# light.net
KiCad netlist of a schematic drawn in Altium Designer
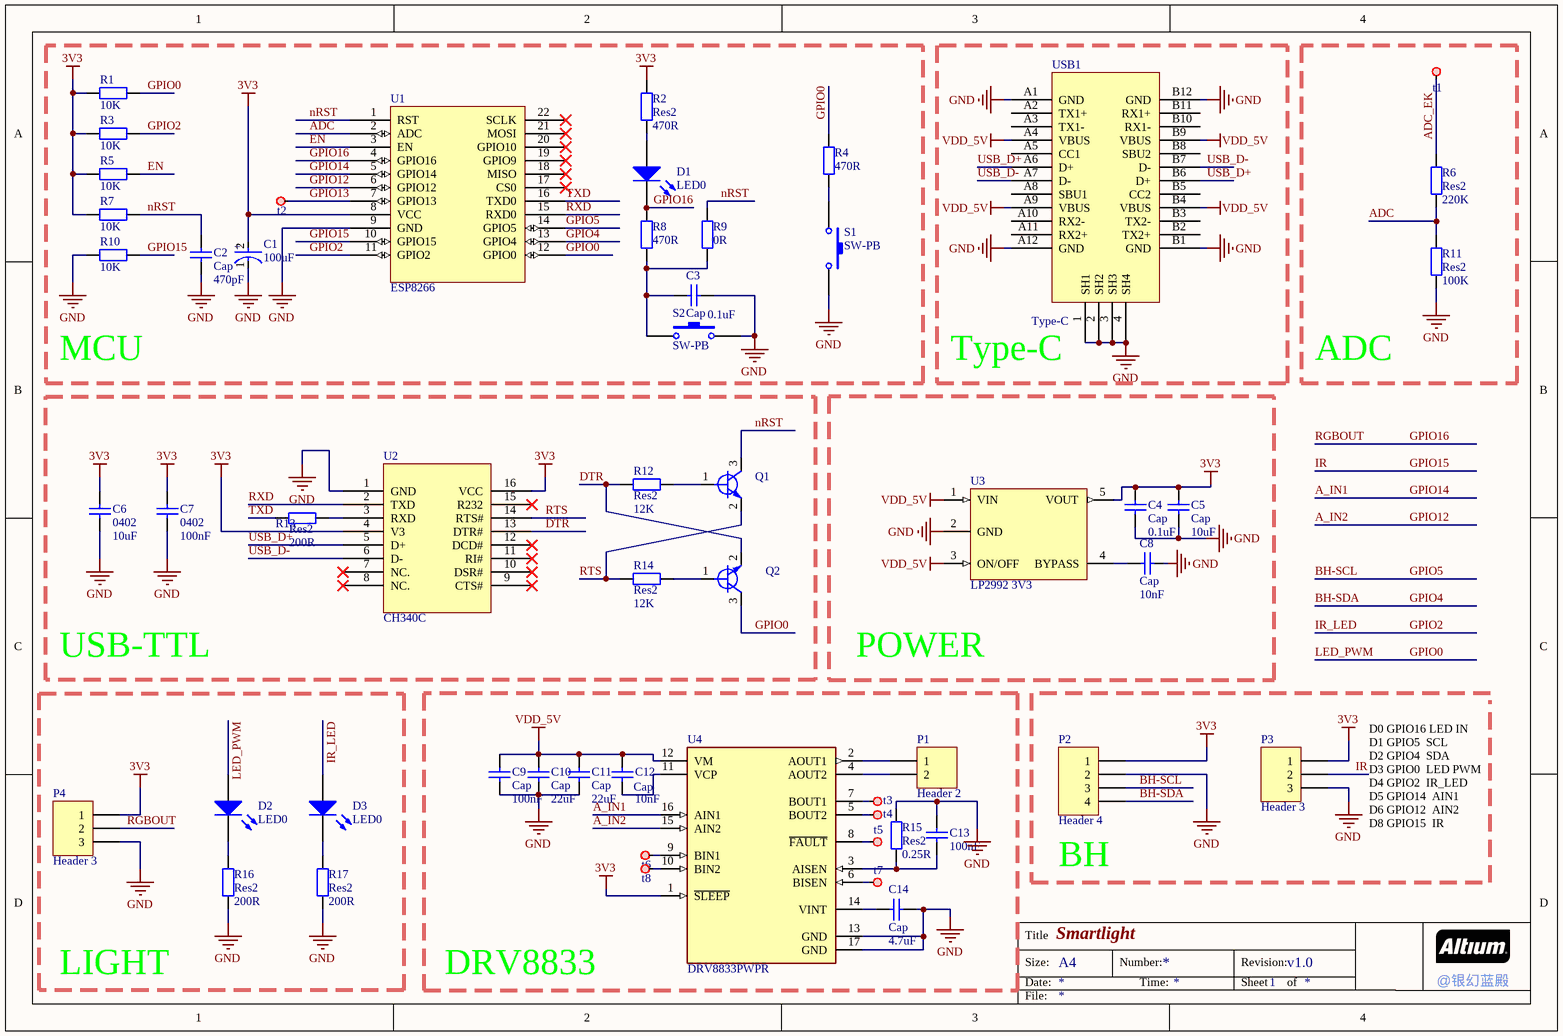
[diagram p0: light.SchDoc]

(export (version "E")
  (design (tool "Eeschema 10.0.6"))
  (components
    (comp (ref "C1")
      (value "100uF")
      (footprint "FP-T495D107K016ATE125-MFG")
      (description "CAP TANT 100UF 10% 16V 2917")
      (fields (field (name "VOLTAGE") "16V") (field (name "TOLERANCE") "10%"))
      (libsource (lib "Altium Content Vault") (part "a00bbbee19879c290e62620ae7e47b1"))
    )
    (comp (ref "C2")
      (value "Cap")
      (footprint "C 0402_M")
      (description "Capacitor (Semiconductor SIM Model)")
      (fields (field (name "ALTIUM_VALUE") "470pF") (field (name "PUBLISHER") "Altium Limited"))
      (libsource (lib "Miscellaneous Devices") (part "Cap Semi"))
    )
    (comp (ref "C3")
      (value "Cap")
      (footprint "C 0402_M")
      (description "Capacitor (Semiconductor SIM Model)")
      (fields (field (name "ALTIUM_VALUE") "0.1uF") (field (name "PUBLISHER") "Altium Limited"))
      (libsource (lib "Miscellaneous Devices") (part "Cap Semi"))
    )
    (comp (ref "C4")
      (value "Cap")
      (footprint "C 0402_M")
      (description "Capacitor (Semiconductor SIM Model)")
      (fields (field (name "ALTIUM_VALUE") "0.1uF") (field (name "PUBLISHER") "Altium Limited"))
      (libsource (lib "Miscellaneous Devices") (part "Cap Semi"))
    )
    (comp (ref "C5")
      (value "Cap")
      (footprint "C 0402_M")
      (description "Capacitor (Semiconductor SIM Model)")
      (fields (field (name "ALTIUM_VALUE") "10uF") (field (name "PUBLISHER") "Altium Limited"))
      (libsource (lib "Miscellaneous Devices") (part "Cap Semi"))
    )
    (comp (ref "C6")
      (value "0402")
      (footprint "C 0402_M")
      (description "Capacitor (Semiconductor SIM Model)")
      (fields (field (name "ALTIUM_VALUE") "10uF") (field (name "PUBLISHER") "Altium Limited"))
      (libsource (lib "Miscellaneous Devices") (part "Cap Semi"))
    )
    (comp (ref "C7")
      (value "0402")
      (footprint "C 0402_M")
      (description "Capacitor (Semiconductor SIM Model)")
      (fields (field (name "ALTIUM_VALUE") "100nF") (field (name "PUBLISHER") "Altium Limited"))
      (libsource (lib "Miscellaneous Devices") (part "Cap Semi"))
    )
    (comp (ref "C8")
      (value "Cap")
      (footprint "C 0402_M")
      (description "Capacitor (Semiconductor SIM Model)")
      (fields (field (name "ALTIUM_VALUE") "10nF") (field (name "PUBLISHER") "Altium Limited"))
      (libsource (lib "Miscellaneous Devices") (part "Cap Semi"))
    )
    (comp (ref "C9")
      (value "Cap")
      (footprint "C 0402_M")
      (description "Capacitor (Semiconductor SIM Model)")
      (fields (field (name "ALTIUM_VALUE") "100nF") (field (name "PUBLISHER") "Altium Limited"))
      (libsource (lib "Miscellaneous Devices") (part "Cap Semi"))
    )
    (comp (ref "C10")
      (value "Cap")
      (footprint "C 0402_M")
      (description "Capacitor (Semiconductor SIM Model)")
      (fields (field (name "ALTIUM_VALUE") "22uF") (field (name "PUBLISHER") "Altium Limited"))
      (libsource (lib "Miscellaneous Devices") (part "Cap Semi"))
    )
    (comp (ref "C11")
      (value "Cap")
      (footprint "C 0402_M")
      (description "Capacitor (Semiconductor SIM Model)")
      (fields (field (name "ALTIUM_VALUE") "22uF") (field (name "PUBLISHER") "Altium Limited"))
      (libsource (lib "Miscellaneous Devices") (part "Cap Semi"))
    )
    (comp (ref "C12")
      (value "Cap")
      (footprint "C 0402_M")
      (description "Capacitor (Semiconductor SIM Model)")
      (fields (field (name "ALTIUM_VALUE") "10nF") (field (name "PUBLISHER") "Altium Limited"))
      (libsource (lib "Miscellaneous Devices") (part "Cap Semi"))
    )
    (comp (ref "C13")
      (value "100nF")
      (footprint "C 0402_M")
      (description "Capacitor (Semiconductor SIM Model)")
      (fields (field (name "PUBLISHER") "Altium Limited"))
      (libsource (lib "Miscellaneous Devices") (part "Cap Semi"))
    )
    (comp (ref "C14")
      (value "Cap")
      (footprint "C 0402_M")
      (description "Capacitor (Semiconductor SIM Model)")
      (fields (field (name "ALTIUM_VALUE") "4.7uF") (field (name "PUBLISHER") "Altium Limited"))
      (libsource (lib "Miscellaneous Devices") (part "Cap Semi"))
    )
    (comp (ref "D1")
      (value "LED0")
      (footprint "LED 0603R")
      (description "Typical INFRARED GaAs LED")
      (fields (field (name "PUBLISHER") "Altium Limited"))
      (libsource (lib "Miscellaneous Devices") (part "LED0"))
    )
    (comp (ref "D2")
      (value "LED0")
      (footprint "LED 0603R")
      (description "Typical INFRARED GaAs LED")
      (fields (field (name "PUBLISHER") "Altium Limited"))
      (libsource (lib "Miscellaneous Devices") (part "LED0"))
    )
    (comp (ref "D3")
      (value "LED0")
      (footprint "LED 0603R")
      (description "Typical INFRARED GaAs LED")
      (fields (field (name "PUBLISHER") "Altium Limited"))
      (libsource (lib "Miscellaneous Devices") (part "LED0"))
    )
    (comp (ref "P1")
      (value "Header 2")
      (footprint "HDR1X2")
      (description "Header, 2-Pin")
      (fields (field (name "PUBLISHER") "Altium Limited"))
      (libsource (lib "Miscellaneous Connectors") (part "Header 2"))
    )
    (comp (ref "P2")
      (value "Header 4")
      (footprint "HDR1X4")
      (description "Header, 4-Pin")
      (fields (field (name "PUBLISHER") "Altium Limited"))
      (libsource (lib "Miscellaneous Connectors") (part "Header 4"))
    )
    (comp (ref "P3")
      (value "Header 3")
      (footprint "HDR1X3")
      (description "Header, 3-Pin")
      (fields (field (name "PUBLISHER") "Altium Limited"))
      (libsource (lib "Miscellaneous Connectors") (part "Header 3"))
    )
    (comp (ref "P4")
      (value "Header 3")
      (footprint "HDR1X3")
      (description "Header, 3-Pin")
      (fields (field (name "PUBLISHER") "Altium Limited"))
      (libsource (lib "Miscellaneous Connectors") (part "Header 3"))
    )
    (comp (ref "Q1")
      (value "Y1 NPN SOT23-3")
      (footprint "SMT_TRIODE_NPN")
      (libsource (lib "DDJ_20180904_Library") (part "S8050"))
    )
    (comp (ref "Q2")
      (value "Y1 NPN SOT23-3")
      (footprint "SMT_TRIODE_NPN")
      (libsource (lib "DDJ_20180904_Library") (part "S8050"))
    )
    (comp (ref "R1")
      (value "10K")
      (footprint "R 0402_M")
      (description "Resistor")
      (fields (field (name "Comment") "0402") (field (name "PUBLISHER") "Altium Limited"))
      (libsource (lib "") (part "Res2_2"))
    )
    (comp (ref "R2")
      (value "Res2")
      (footprint "R 0402_M")
      (description "Resistor")
      (fields (field (name "ALTIUM_VALUE") "470R") (field (name "PUBLISHER") "Altium Limited"))
      (libsource (lib "Miscellaneous Devices") (part "Res2"))
    )
    (comp (ref "R3")
      (value "10K")
      (footprint "R 0402_M")
      (description "Resistor")
      (fields (field (name "Comment") "0402") (field (name "PUBLISHER") "Altium Limited"))
      (libsource (lib "") (part "Res2_2"))
    )
    (comp (ref "R4")
      (value "470R")
      (footprint "R 0402_M")
      (description "Resistor")
      (fields (field (name "Comment") "Res2") (field (name "PUBLISHER") "Altium Limited"))
      (libsource (lib "") (part "Res2_1"))
    )
    (comp (ref "R5")
      (value "10K")
      (footprint "R 0402_M")
      (description "Resistor")
      (fields (field (name "Comment") "0402") (field (name "PUBLISHER") "Altium Limited"))
      (libsource (lib "") (part "Res2_2"))
    )
    (comp (ref "R6")
      (value "Res2")
      (footprint "R 0402_M")
      (description "Resistor")
      (fields (field (name "ALTIUM_VALUE") "220K") (field (name "PUBLISHER") "Altium Limited"))
      (libsource (lib "Miscellaneous Devices") (part "Res2"))
    )
    (comp (ref "R7")
      (value "10K")
      (footprint "R 0402_M")
      (description "Resistor")
      (fields (field (name "Comment") "0402") (field (name "PUBLISHER") "Altium Limited"))
      (libsource (lib "") (part "Res2_2"))
    )
    (comp (ref "R8")
      (value "470R")
      (footprint "R 0402_M")
      (description "Resistor")
      (fields (field (name "Comment") "Res2") (field (name "PUBLISHER") "Altium Limited"))
      (libsource (lib "") (part "Res2_1"))
    )
    (comp (ref "R9")
      (value "0R")
      (footprint "R 0402_M")
      (description "Resistor")
      (fields (field (name "Comment") "Res2") (field (name "PUBLISHER") "Altium Limited"))
      (libsource (lib "") (part "Res2_1"))
    )
    (comp (ref "R10")
      (value "10K")
      (footprint "R 0402_M")
      (description "Resistor")
      (fields (field (name "Comment") "0402") (field (name "PUBLISHER") "Altium Limited"))
      (libsource (lib "") (part "Res2_2"))
    )
    (comp (ref "R11")
      (value "Res2")
      (footprint "R 0402_M")
      (description "Resistor")
      (fields (field (name "ALTIUM_VALUE") "100K") (field (name "PUBLISHER") "Altium Limited"))
      (libsource (lib "Miscellaneous Devices") (part "Res2"))
    )
    (comp (ref "R12")
      (value "Res2")
      (footprint "R 0402_M")
      (description "Resistor")
      (fields (field (name "ALTIUM_VALUE") "12K") (field (name "PUBLISHER") "Altium Limited"))
      (libsource (lib "") (part "Res2_2"))
    )
    (comp (ref "R13")
      (value "Res2")
      (footprint "R 0402_M")
      (description "Resistor")
      (fields (field (name "ALTIUM_VALUE") "200R") (field (name "PUBLISHER") "Altium Limited"))
      (libsource (lib "") (part "Res2_2"))
    )
    (comp (ref "R14")
      (value "Res2")
      (footprint "R 0402_M")
      (description "Resistor")
      (fields (field (name "ALTIUM_VALUE") "12K") (field (name "PUBLISHER") "Altium Limited"))
      (libsource (lib "") (part "Res2_2"))
    )
    (comp (ref "R15")
      (value "Res2")
      (footprint "R 1206_M")
      (description "Resistor")
      (fields (field (name "ALTIUM_VALUE") "0.25R") (field (name "PUBLISHER") "Altium Limited"))
      (libsource (lib "") (part "Res2_2"))
    )
    (comp (ref "R16")
      (value "Res2")
      (footprint "R 0402_M")
      (description "Resistor")
      (fields (field (name "ALTIUM_VALUE") "200R") (field (name "PUBLISHER") "Altium Limited"))
      (libsource (lib "Miscellaneous Devices") (part "Res2"))
    )
    (comp (ref "R17")
      (value "Res2")
      (footprint "R 0402_M")
      (description "Resistor")
      (fields (field (name "ALTIUM_VALUE") "200R") (field (name "PUBLISHER") "Altium Limited"))
      (libsource (lib "Miscellaneous Devices") (part "Res2"))
    )
    (comp (ref "S1")
      (value "SW-PB")
      (footprint "TSW DIP-6*6*5")
      (description "Switch")
      (fields (field (name "PUBLISHER") "Altium Limited"))
      (libsource (lib "Miscellaneous Devices") (part "SW-PB"))
    )
    (comp (ref "S2")
      (value "SW-PB")
      (footprint "TSW DIP-6*6*5")
      (description "Switch")
      (fields (field (name "PUBLISHER") "Altium Limited"))
      (libsource (lib "Miscellaneous Devices") (part "SW-PB"))
    )
    (comp (ref "t1") (value "test") (footprint "test") (libsource (lib "RC-AE86") (part "test")))
    (comp (ref "t2") (value "test") (footprint "test") (libsource (lib "RC-AE86") (part "test")))
    (comp (ref "t3") (value "test") (footprint "test") (libsource (lib "RC-AE86") (part "test")))
    (comp (ref "t4") (value "test") (footprint "test") (libsource (lib "RC-AE86") (part "test")))
    (comp (ref "t5") (value "test") (footprint "test") (libsource (lib "RC-AE86") (part "test")))
    (comp (ref "t6") (value "test") (footprint "test") (libsource (lib "RC-AE86") (part "test")))
    (comp (ref "t7") (value "test") (footprint "test") (libsource (lib "RC-AE86") (part "test")))
    (comp (ref "t8") (value "test") (footprint "test") (libsource (lib "RC-AE86") (part "test")))
    (comp (ref "U1") (value "ESP8266") (footprint "esp8266") (libsource (lib "HD") (part "ESP8266")))
    (comp (ref "U2") (value "CH340C") (footprint "CH340") (libsource (lib "HD") (part "CH340C")))
    (comp (ref "U3")
      (value "LP2992 3V3")
      (footprint "SOT23-5N")
      (description "LDO")
      (libsource (lib "MyPcbLib") (part "LP2992"))
    )
    (comp (ref "U4")
      (value "DRV8833PWPR")
      (footprint "FP-PWP0016C-IPC_A")
      (description "IC MOTOR DRIVER PAR 16HTSSOP")
      (libsource (lib "Altium Content Vault") (part "bca689d78e207bdabf30b9b31c2f798"))
    )
    (comp (ref "USB1")
      (value "Type-C")
      (footprint "Type-C-TOP")
      (libsource (lib "MainBoard") (part "USB-Type-C-TOP"))
    )
  )
  (nets
    (net (code "1") (name "/ADC") (class "Default")
      (node (ref "R11") (pin "1") (pinfunction "1_1") (pintype "passive"))
      (node (ref "R6") (pin "2") (pinfunction "2_2") (pintype "passive"))
      (node (ref "U1") (pin "2") (pinfunction "ADC_2") (pintype "bidirectional"))
    )
    (net (code "2") (name "/ADC_EK") (class "Default")
      (node (ref "R6") (pin "1") (pinfunction "1_1") (pintype "passive"))
      (node (ref "t1") (pin "1") (pinfunction "test_1") (pintype "passive"))
    )
    (net (code "3") (name "/A_IN1") (class "Default")
      (node (ref "U1") (pin "5") (pinfunction "GPIO14_5") (pintype "bidirectional"))
      (node (ref "U4") (pin "16") (pinfunction "AIN1_16") (pintype "input"))
    )
    (net (code "4") (name "/A_IN2") (class "Default")
      (node (ref "U1") (pin "6") (pinfunction "GPIO12_6") (pintype "bidirectional"))
      (node (ref "U4") (pin "15") (pinfunction "AIN2_15") (pintype "input"))
    )
    (net (code "5") (name "/BH-SCL") (class "Default")
      (node (ref "P2") (pin "3") (pinfunction "3_3") (pintype "passive"))
      (node (ref "U1") (pin "14") (pinfunction "GPIO5_14") (pintype "bidirectional"))
    )
    (net (code "6") (name "/BH-SDA") (class "Default")
      (node (ref "P2") (pin "4") (pinfunction "4_4") (pintype "passive"))
      (node (ref "U1") (pin "13") (pinfunction "GPIO4_13") (pintype "bidirectional"))
    )
    (net (code "7") (name "/DTR") (class "Default")
      (node (ref "Q2") (pin "2") (pinfunction "EMITTER_2") (pintype "passive"))
      (node (ref "R12") (pin "1") (pinfunction "1_1") (pintype "passive"))
      (node (ref "U2") (pin "13") (pinfunction "DTR#_13") (pintype "passive"))
    )
    (net (code "8") (name "/EN") (class "Default")
      (node (ref "R5") (pin "2") (pinfunction "2_2") (pintype "passive"))
      (node (ref "U1") (pin "3") (pinfunction "EN_3") (pintype "passive"))
    )
    (net (code "9") (name "/GPIO0") (class "Default")
      (node (ref "D2") (pin "1") (pinfunction "A_1") (pintype "passive"))
      (node (ref "Q2") (pin "3") (pinfunction "COLLECTOR_3") (pintype "passive"))
      (node (ref "R1") (pin "2") (pinfunction "2_2") (pintype "passive"))
      (node (ref "R4") (pin "2") (pinfunction "2_2") (pintype "passive"))
      (node (ref "U1") (pin "12") (pinfunction "GPIO0_12") (pintype "bidirectional"))
    )
    (net (code "10") (name "/GPIO2") (class "Default")
      (node (ref "D3") (pin "1") (pinfunction "A_1") (pintype "passive"))
      (node (ref "R3") (pin "2") (pinfunction "2_2") (pintype "passive"))
      (node (ref "U1") (pin "11") (pinfunction "GPIO2_11") (pintype "bidirectional"))
    )
    (net (code "11") (name "/GPIO13") (class "Default")
      (node (ref "U1") (pin "7") (pinfunction "GPIO13_7") (pintype "bidirectional"))
      (node (ref "t2") (pin "1") (pinfunction "test_1") (pintype "passive"))
    )
    (net (code "12") (name "/GPIO15") (class "Default")
      (node (ref "P3") (pin "2") (pinfunction "2_2") (pintype "passive"))
      (node (ref "R10") (pin "2") (pinfunction "2_2") (pintype "passive"))
      (node (ref "U1") (pin "10") (pinfunction "GPIO15_10") (pintype "bidirectional"))
    )
    (net (code "13") (name "/GPIO16") (class "Default")
      (node (ref "D1") (pin "2") (pinfunction "K_2") (pintype "passive"))
      (node (ref "P4") (pin "2") (pinfunction "2_2") (pintype "passive"))
      (node (ref "R8") (pin "2") (pinfunction "2_2") (pintype "passive"))
      (node (ref "U1") (pin "4") (pinfunction "GPIO16_4") (pintype "bidirectional"))
    )
    (net (code "14") (name "/RTS") (class "Default")
      (node (ref "Q1") (pin "2") (pinfunction "EMITTER_2") (pintype "passive"))
      (node (ref "R14") (pin "1") (pinfunction "1_1") (pintype "passive"))
      (node (ref "U2") (pin "14") (pinfunction "RTS#_14") (pintype "passive"))
    )
    (net (code "15") (name "/RXD") (class "Default")
      (node (ref "U1") (pin "15") (pinfunction "RXD0_15") (pintype "passive"))
      (node (ref "U2") (pin "2") (pinfunction "TXD_2") (pintype "passive"))
    )
    (net (code "16") (name "/TXD") (class "Default")
      (node (ref "R13") (pin "1") (pinfunction "1_1") (pintype "passive"))
      (node (ref "U1") (pin "16") (pinfunction "TXD0_16") (pintype "passive"))
    )
    (net (code "17") (name "/USB_D+") (class "Default")
      (node (ref "U2") (pin "5") (pinfunction "D+_5") (pintype "passive"))
      (node (ref "USB1") (pin "A6") (pinfunction "D+_A6") (pintype "passive"))
      (node (ref "USB1") (pin "B6") (pinfunction "D+_B6") (pintype "passive"))
    )
    (net (code "18") (name "/USB_D-") (class "Default")
      (node (ref "U2") (pin "6") (pinfunction "D-_6") (pintype "passive"))
      (node (ref "USB1") (pin "A7") (pinfunction "D-_A7") (pintype "passive"))
      (node (ref "USB1") (pin "B7") (pinfunction "D-_B7") (pintype "passive"))
    )
    (net (code "19") (name "/nRST") (class "Default")
      (node (ref "C2") (pin "1") (pinfunction "1_1") (pintype "passive"))
      (node (ref "Q1") (pin "3") (pinfunction "COLLECTOR_3") (pintype "passive"))
      (node (ref "R7") (pin "2") (pinfunction "2_2") (pintype "passive"))
      (node (ref "R9") (pin "2") (pinfunction "2_2") (pintype "passive"))
      (node (ref "U1") (pin "1") (pinfunction "RST_1") (pintype "passive"))
    )
    (net (code "20") (name "3V3") (class "Default")
      (node (ref "C1") (pin "2") (pinfunction "A_2") (pintype "passive"))
      (node (ref "C4") (pin "1") (pinfunction "1_1") (pintype "passive"))
      (node (ref "C5") (pin "1") (pinfunction "1_1") (pintype "passive"))
      (node (ref "C6") (pin "2") (pinfunction "2_2") (pintype "passive"))
      (node (ref "C7") (pin "2") (pinfunction "2_2") (pintype "passive"))
      (node (ref "P2") (pin "1") (pinfunction "1_1") (pintype "passive"))
      (node (ref "P3") (pin "1") (pinfunction "1_1") (pintype "passive"))
      (node (ref "P4") (pin "1") (pinfunction "1_1") (pintype "passive"))
      (node (ref "R1") (pin "1") (pinfunction "1_1") (pintype "passive"))
      (node (ref "R2") (pin "1") (pinfunction "1_1") (pintype "passive"))
      (node (ref "R3") (pin "1") (pinfunction "1_1") (pintype "passive"))
      (node (ref "R5") (pin "1") (pinfunction "1_1") (pintype "passive"))
      (node (ref "R7") (pin "1") (pinfunction "1_1") (pintype "passive"))
      (node (ref "U1") (pin "8") (pinfunction "VCC_8") (pintype "passive"))
      (node (ref "U2") (pin "16") (pinfunction "VCC_16") (pintype "passive"))
      (node (ref "U2") (pin "4") (pinfunction "V3_4") (pintype "passive"))
      (node (ref "U3") (pin "5") (pinfunction "VOUT_5") (pintype "output"))
      (node (ref "U4") (pin "1") (pinfunction "~{SLEEP}_1") (pintype "input"))
    )
    (net (code "21") (name "GND") (class "Default")
      (node (ref "C1") (pin "1") (pinfunction "C_1") (pintype "passive"))
      (node (ref "C10") (pin "2") (pinfunction "2_2") (pintype "passive"))
      (node (ref "C11") (pin "2") (pinfunction "2_2") (pintype "passive"))
      (node (ref "C13") (pin "2") (pinfunction "2_2") (pintype "passive"))
      (node (ref "C14") (pin "1") (pinfunction "1_1") (pintype "passive"))
      (node (ref "C2") (pin "2") (pinfunction "2_2") (pintype "passive"))
      (node (ref "C3") (pin "2") (pinfunction "2_2") (pintype "passive"))
      (node (ref "C4") (pin "2") (pinfunction "2_2") (pintype "passive"))
      (node (ref "C5") (pin "2") (pinfunction "2_2") (pintype "passive"))
      (node (ref "C6") (pin "1") (pinfunction "1_1") (pintype "passive"))
      (node (ref "C7") (pin "1") (pinfunction "1_1") (pintype "passive"))
      (node (ref "C8") (pin "2") (pinfunction "2_2") (pintype "passive"))
      (node (ref "C9") (pin "2") (pinfunction "2_2") (pintype "passive"))
      (node (ref "P2") (pin "2") (pinfunction "2_2") (pintype "passive"))
      (node (ref "P3") (pin "3") (pinfunction "3_3") (pintype "passive"))
      (node (ref "P4") (pin "3") (pinfunction "3_3") (pintype "passive"))
      (node (ref "R10") (pin "1") (pinfunction "1_1") (pintype "passive"))
      (node (ref "R11") (pin "2") (pinfunction "2_2") (pintype "passive"))
      (node (ref "R15") (pin "2") (pinfunction "2_2") (pintype "passive"))
      (node (ref "R16") (pin "2") (pinfunction "2_2") (pintype "passive"))
      (node (ref "R17") (pin "2") (pinfunction "2_2") (pintype "passive"))
      (node (ref "S1") (pin "2") (pinfunction "2_2") (pintype "passive"))
      (node (ref "S2") (pin "2") (pinfunction "2_2") (pintype "passive"))
      (node (ref "U1") (pin "9") (pinfunction "GND_9") (pintype "passive"))
      (node (ref "U2") (pin "1") (pinfunction "GND_1") (pintype "passive"))
      (node (ref "U3") (pin "2") (pinfunction "GND_2") (pintype "passive"))
      (node (ref "U4") (pin "13") (pinfunction "GND_13") (pintype "power_in"))
      (node (ref "U4") (pin "17") (pinfunction "GND_17") (pintype "power_in"))
      (node (ref "USB1") (pin "1") (pinfunction "SH1_1") (pintype "passive"))
      (node (ref "USB1") (pin "2") (pinfunction "SH2_2") (pintype "passive"))
      (node (ref "USB1") (pin "3") (pinfunction "SH3_3") (pintype "passive"))
      (node (ref "USB1") (pin "4") (pinfunction "SH4_4") (pintype "passive"))
      (node (ref "USB1") (pin "A1") (pinfunction "GND_A1") (pintype "passive"))
      (node (ref "USB1") (pin "A12") (pinfunction "GND_A12") (pintype "passive"))
      (node (ref "USB1") (pin "B1") (pinfunction "GND_B1") (pintype "passive"))
      (node (ref "USB1") (pin "B12") (pinfunction "GND_B12") (pintype "passive"))
    )
    (net (code "22") (name "Net-(C3-Pad1)") (class "Default")
      (node (ref "C3") (pin "1") (pinfunction "1_1") (pintype "passive"))
      (node (ref "R8") (pin "1") (pinfunction "1_1") (pintype "passive"))
      (node (ref "R9") (pin "1") (pinfunction "1_1") (pintype "passive"))
      (node (ref "S2") (pin "1") (pinfunction "1_1") (pintype "passive"))
    )
    (net (code "23") (name "Net-(D1-A)") (class "Default")
      (node (ref "D1") (pin "1") (pinfunction "A_1") (pintype "passive"))
      (node (ref "R2") (pin "2") (pinfunction "2_2") (pintype "passive"))
    )
    (net (code "24") (name "Net-(D2-K)") (class "Default")
      (node (ref "D2") (pin "2") (pinfunction "K_2") (pintype "passive"))
      (node (ref "R16") (pin "1") (pinfunction "1_1") (pintype "passive"))
    )
    (net (code "25") (name "Net-(D3-K)") (class "Default")
      (node (ref "D3") (pin "2") (pinfunction "K_2") (pintype "passive"))
      (node (ref "R17") (pin "1") (pinfunction "1_1") (pintype "passive"))
    )
    (net (code "26") (name "Net-(Q1-BASE)") (class "Default")
      (node (ref "Q1") (pin "1") (pinfunction "BASE_1") (pintype "passive"))
      (node (ref "R12") (pin "2") (pinfunction "2_2") (pintype "passive"))
    )
    (net (code "27") (name "Net-(Q2-BASE)") (class "Default")
      (node (ref "Q2") (pin "1") (pinfunction "BASE_1") (pintype "passive"))
      (node (ref "R14") (pin "2") (pinfunction "2_2") (pintype "passive"))
    )
    (net (code "28") (name "Net-(R4-Pad1)") (class "Default")
      (node (ref "R4") (pin "1") (pinfunction "1_1") (pintype "passive"))
      (node (ref "S1") (pin "1") (pinfunction "1_1") (pintype "passive"))
    )
    (net (code "29") (name "Net-(U2-RXD)") (class "Default")
      (node (ref "R13") (pin "2") (pinfunction "2_2") (pintype "passive"))
      (node (ref "U2") (pin "3") (pinfunction "RXD_3") (pintype "passive"))
    )
    (net (code "30") (name "Net-(U3-BYPASS)") (class "Default")
      (node (ref "C8") (pin "1") (pinfunction "1_1") (pintype "passive"))
      (node (ref "U3") (pin "4") (pinfunction "BYPASS_4") (pintype "passive"))
    )
    (net (code "31") (name "Net-(U4-AISEN)") (class "Default")
      (node (ref "C13") (pin "1") (pinfunction "1_1") (pintype "passive"))
      (node (ref "R15") (pin "1") (pinfunction "1_1") (pintype "passive"))
      (node (ref "U4") (pin "3") (pinfunction "AISEN_3") (pintype "input"))
    )
    (net (code "32") (name "Net-(U4-AOUT1)") (class "Default")
      (node (ref "P1") (pin "1") (pinfunction "1_1") (pintype "passive"))
      (node (ref "U4") (pin "2") (pinfunction "AOUT1_2") (pintype "output"))
    )
    (net (code "33") (name "Net-(U4-AOUT2)") (class "Default")
      (node (ref "P1") (pin "2") (pinfunction "2_2") (pintype "passive"))
      (node (ref "U4") (pin "4") (pinfunction "AOUT2_4") (pintype "tri_state"))
    )
    (net (code "34") (name "Net-(U4-BIN1)") (class "Default")
      (node (ref "U4") (pin "9") (pinfunction "BIN1_9") (pintype "input"))
      (node (ref "t6") (pin "1") (pinfunction "test_1") (pintype "passive"))
    )
    (net (code "35") (name "Net-(U4-BIN2)") (class "Default")
      (node (ref "U4") (pin "10") (pinfunction "BIN2_10") (pintype "input"))
      (node (ref "t8") (pin "1") (pinfunction "test_1") (pintype "passive"))
    )
    (net (code "36") (name "Net-(U4-BISEN)") (class "Default")
      (node (ref "U4") (pin "6") (pinfunction "BISEN_6") (pintype "input"))
      (node (ref "t7") (pin "1") (pinfunction "test_1") (pintype "passive"))
    )
    (net (code "37") (name "Net-(U4-BOUT1)") (class "Default")
      (node (ref "U4") (pin "7") (pinfunction "BOUT1_7") (pintype "tri_state"))
      (node (ref "t3") (pin "1") (pinfunction "test_1") (pintype "passive"))
    )
    (net (code "38") (name "Net-(U4-BOUT2)") (class "Default")
      (node (ref "U4") (pin "5") (pinfunction "BOUT2_5") (pintype "tri_state"))
      (node (ref "t4") (pin "1") (pinfunction "test_1") (pintype "passive"))
    )
    (net (code "39") (name "Net-(U4-VCP)") (class "Default")
      (node (ref "C12") (pin "1") (pinfunction "1_1") (pintype "passive"))
      (node (ref "U4") (pin "11") (pinfunction "VCP_11") (pintype "passive"))
    )
    (net (code "40") (name "Net-(U4-VINT)") (class "Default")
      (node (ref "C14") (pin "2") (pinfunction "2_2") (pintype "passive"))
      (node (ref "U4") (pin "14") (pinfunction "VINT_14") (pintype "power_in"))
    )
    (net (code "41") (name "Net-(U4-~{FAULT})") (class "Default")
      (node (ref "U4") (pin "8") (pinfunction "~{FAULT}_8") (pintype "open_collector"))
      (node (ref "t5") (pin "1") (pinfunction "test_1") (pintype "passive"))
    )
    (net (code "42") (name "VDD_5V") (class "Default")
      (node (ref "C10") (pin "1") (pinfunction "1_1") (pintype "passive"))
      (node (ref "C11") (pin "1") (pinfunction "1_1") (pintype "passive"))
      (node (ref "C12") (pin "2") (pinfunction "2_2") (pintype "passive"))
      (node (ref "C9") (pin "1") (pinfunction "1_1") (pintype "passive"))
      (node (ref "U3") (pin "1") (pinfunction "VIN_1") (pintype "input"))
      (node (ref "U3") (pin "3") (pinfunction "ON/OFF_3") (pintype "input"))
      (node (ref "U4") (pin "12") (pinfunction "VM_12") (pintype "power_in"))
      (node (ref "USB1") (pin "A4") (pinfunction "VBUS_A4") (pintype "passive"))
      (node (ref "USB1") (pin "A9") (pinfunction "VBUS_A9") (pintype "passive"))
      (node (ref "USB1") (pin "B4") (pinfunction "VBUS_B4") (pintype "passive"))
      (node (ref "USB1") (pin "B9") (pinfunction "VBUS_B9") (pintype "passive"))
    )
    (net (code "43") (name "unconnected-(U1-CS0-Pad17)") (class "Default")
      (node (ref "U1") (pin "17") (pinfunction "CS0_17") (pintype "passive+no_connect"))
    )
    (net (code "44") (name "unconnected-(U1-GPIO9-Pad19)") (class "Default")
      (node (ref "U1") (pin "19") (pinfunction "GPIO9_19") (pintype "passive+no_connect"))
    )
    (net (code "45") (name "unconnected-(U1-GPIO10-Pad20)") (class "Default")
      (node (ref "U1") (pin "20") (pinfunction "GPIO10_20") (pintype "passive+no_connect"))
    )
    (net (code "46") (name "unconnected-(U1-MISO-Pad18)") (class "Default")
      (node (ref "U1") (pin "18") (pinfunction "MISO_18") (pintype "passive+no_connect"))
    )
    (net (code "47") (name "unconnected-(U1-MOSI-Pad21)") (class "Default")
      (node (ref "U1") (pin "21") (pinfunction "MOSI_21") (pintype "passive+no_connect"))
    )
    (net (code "48") (name "unconnected-(U1-SCLK-Pad22)") (class "Default")
      (node (ref "U1") (pin "22") (pinfunction "SCLK_22") (pintype "passive+no_connect"))
    )
    (net (code "49") (name "unconnected-(U2-CTS#-Pad9)") (class "Default")
      (node (ref "U2") (pin "9") (pinfunction "CTS#_9") (pintype "passive+no_connect"))
    )
    (net (code "50") (name "unconnected-(U2-DCD#-Pad12)") (class "Default")
      (node (ref "U2") (pin "12") (pinfunction "DCD#_12") (pintype "passive+no_connect"))
    )
    (net (code "51") (name "unconnected-(U2-DSR#-Pad10)") (class "Default")
      (node (ref "U2") (pin "10") (pinfunction "DSR#_10") (pintype "passive+no_connect"))
    )
    (net (code "52") (name "unconnected-(U2-NC.-Pad7)") (class "Default")
      (node (ref "U2") (pin "7") (pinfunction "NC._7") (pintype "passive+no_connect"))
    )
    (net (code "53") (name "unconnected-(U2-NC.-Pad8)") (class "Default")
      (node (ref "U2") (pin "8") (pinfunction "NC._8") (pintype "passive+no_connect"))
    )
    (net (code "54") (name "unconnected-(U2-R232-Pad15)") (class "Default")
      (node (ref "U2") (pin "15") (pinfunction "R232_15") (pintype "passive+no_connect"))
    )
    (net (code "55") (name "unconnected-(U2-RI#-Pad11)") (class "Default")
      (node (ref "U2") (pin "11") (pinfunction "RI#_11") (pintype "passive+no_connect"))
    )
    (net (code "56") (name "unconnected-(USB1-CC1-PadA5)") (class "Default")
      (node (ref "USB1") (pin "A5") (pinfunction "CC1_A5") (pintype "passive"))
    )
    (net (code "57") (name "unconnected-(USB1-CC2-PadB5)") (class "Default")
      (node (ref "USB1") (pin "B5") (pinfunction "CC2_B5") (pintype "passive"))
    )
    (net (code "58") (name "unconnected-(USB1-RX1+-PadB11)") (class "Default")
      (node (ref "USB1") (pin "B11") (pinfunction "RX1+_B11") (pintype "passive"))
    )
    (net (code "59") (name "unconnected-(USB1-RX1--PadB10)") (class "Default")
      (node (ref "USB1") (pin "B10") (pinfunction "RX1-_B10") (pintype "passive"))
    )
    (net (code "60") (name "unconnected-(USB1-RX2+-PadA11)") (class "Default")
      (node (ref "USB1") (pin "A11") (pinfunction "RX2+_A11") (pintype "passive"))
    )
    (net (code "61") (name "unconnected-(USB1-RX2--PadA10)") (class "Default")
      (node (ref "USB1") (pin "A10") (pinfunction "RX2-_A10") (pintype "passive"))
    )
    (net (code "62") (name "unconnected-(USB1-SBU1-PadA8)") (class "Default")
      (node (ref "USB1") (pin "A8") (pinfunction "SBU1_A8") (pintype "passive"))
    )
    (net (code "63") (name "unconnected-(USB1-SBU2-PadB8)") (class "Default")
      (node (ref "USB1") (pin "B8") (pinfunction "SBU2_B8") (pintype "passive"))
    )
    (net (code "64") (name "unconnected-(USB1-TX1+-PadA2)") (class "Default")
      (node (ref "USB1") (pin "A2") (pinfunction "TX1+_A2") (pintype "passive"))
    )
    (net (code "65") (name "unconnected-(USB1-TX1--PadA3)") (class "Default")
      (node (ref "USB1") (pin "A3") (pinfunction "TX1-_A3") (pintype "passive"))
    )
    (net (code "66") (name "unconnected-(USB1-TX2+-PadB2)") (class "Default")
      (node (ref "USB1") (pin "B2") (pinfunction "TX2+_B2") (pintype "passive"))
    )
    (net (code "67") (name "unconnected-(USB1-TX2--PadB3)") (class "Default")
      (node (ref "USB1") (pin "B3") (pinfunction "TX2-_B3") (pintype "passive"))
    )
  )
)
